# USB_UART.net
KiCad netlist of a schematic drawn in Altium Designer
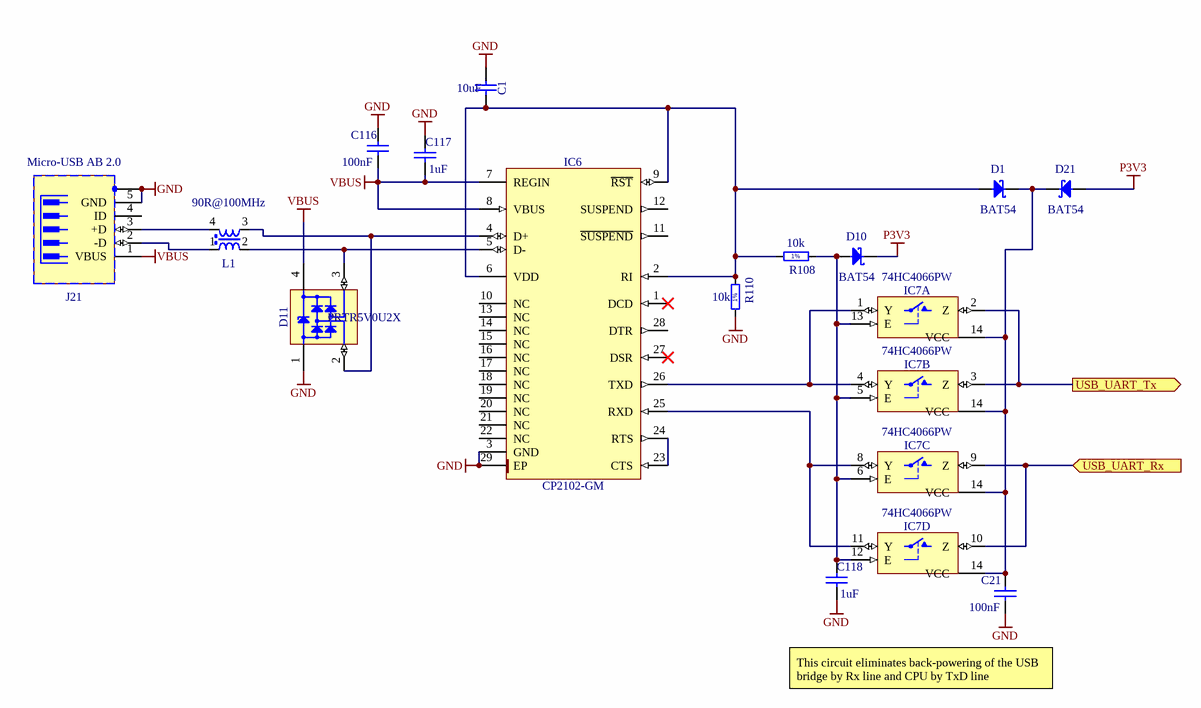
[diagram p0: USB_UART.SchDoc]

(export (version "E")
  (design (tool "Eeschema 10.0.6"))
  (components
    (comp (ref "C1")
      (value "10uF")
      (footprint "CAPC2012X135N")
      (description "Non-polarised capacitor")
      (fields
        (field (name "PART NUMBER") "CC0805_10UF_16V_10%_X5R")
        (field (name "VOLTAGE") "16V")
        (field (name "AUTHOR") "CERN DEM JLC")
      )
      (libsource (lib "Capacitors") (part "Capacitor - non polarized"))
    )
    (comp (ref "C21")
      (value "100nF")
      (footprint "CAPC1005X55N")
      (description "Non-polarised capacitor")
      (fields
        (field (name "PART NUMBER") "CC0402_100NF_16V_10%_X5R")
        (field (name "VOLTAGE") "16V")
        (field (name "AUTHOR") "CERN DEM JLC")
      )
      (libsource (lib "Capacitors") (part "Capacitor - non polarized"))
    )
    (comp (ref "C116")
      (value "100nF")
      (footprint "CAPC1005X55N")
      (description "Non-polarised capacitor")
      (fields
        (field (name "PART NUMBER") "CC0402_100NF_16V_10%_X5R")
        (field (name "VOLTAGE") "16V")
        (field (name "AUTHOR") "CERN DEM JLC")
      )
      (libsource (lib "Capacitors") (part "Capacitor - non polarized"))
    )
    (comp (ref "C117")
      (value "1uF")
      (footprint "CAPC1005X55N")
      (description "Non-polarised capacitor")
      (fields
        (field (name "PART NUMBER") "CC0402_1UF_16V_10%_X5R")
        (field (name "VOLTAGE") "16V")
        (field (name "AUTHOR") "CERN DEM JLC")
      )
      (libsource (lib "Capacitors") (part "Capacitor - non polarized"))
    )
    (comp (ref "C118")
      (value "1uF")
      (footprint "CAPC1005X55N")
      (description "Non-polarised capacitor")
      (fields
        (field (name "PART NUMBER") "CC0402_1UF_16V_10%_X5R")
        (field (name "VOLTAGE") "16V")
        (field (name "AUTHOR") "CERN DEM JLC")
      )
      (libsource (lib "Capacitors") (part "Capacitor - non polarized"))
    )
    (comp (ref "D1")
      (value "BAT54")
      (footprint "SOT95P240X130-3N")
      (description "Diode Schottky  Anode Pin 1 Cathode Pin 3 (Pas de pin 2)")
      (fields
        (field (name "VOLTAGE") "30V")
        (field (name "POWER") "200mA")
        (field (name "AUTHOR") "CERN DEM JLC")
      )
      (libsource (lib "ICs And Semiconductors") (part "Diode Schottky A1C3"))
    )
    (comp (ref "D10")
      (value "BAT54")
      (footprint "SOT95P240X130-3N")
      (description "Diode Schottky  Anode Pin 1 Cathode Pin 3 (Pas de pin 2)")
      (fields
        (field (name "VOLTAGE") "30V")
        (field (name "POWER") "200mA")
        (field (name "AUTHOR") "CERN DEM JLC")
      )
      (libsource (lib "ICs And Semiconductors") (part "Diode Schottky A1C3"))
    )
    (comp (ref "D11")
      (value "PRTR5V0U2X")
      (footprint "SOT190P230X110-4N")
      (description "Ultra Low Capacitance Double Rail-to-Rail ESD Protection Diode")
      (fields
        (field (name "VOLTAGE") "5.5V")
        (field (name "MANUFACTURER") "NXP SEMICONDUCTORS")
        (field (name "AUTHOR") "CERN DEM JLC")
      )
      (libsource (lib "ICs And Semiconductors") (part "PRTR5V0U2X"))
    )
    (comp (ref "D21")
      (value "BAT54")
      (footprint "SOT95P240X130-3N")
      (description "Diode Schottky  Anode Pin 1 Cathode Pin 3 (Pas de pin 2)")
      (fields
        (field (name "VOLTAGE") "30V")
        (field (name "POWER") "200mA")
        (field (name "AUTHOR") "CERN DEM JLC")
      )
      (libsource (lib "ICs And Semiconductors") (part "Diode Schottky A1C3"))
    )
    (comp (ref "IC6")
      (value "CP2102-GM")
      (footprint "QFN50P500X500X100-29N-S335")
      (description "Single-Chip USB to UART Bridge")
      (fields (field (name "MANUFACTURER") "SILICON LABS") (field (name "AUTHOR") "CERN DEM JLC"))
      (libsource (lib "ICs And Semiconductors") (part "CP2102-GM"))
    )
    (comp (ref "IC7")
      (value "74HC4066PW")
      (footprint "SOP65P640X110-14N")
      (fields (field (name "MANUFACTURER") "NXP SEMICONDUCTORS") (field (name "AUTHOR") "CERN DEM JLC"))
      (libsource (lib "ICs And Semiconductors") (part "4066"))
    )
    (comp (ref "J21")
      (value "Micro-USB AB 2.0")
      (footprint "HIROSE_ZX62RD-AB-5P8(30)")
      (description "5 Pin + 1 Shield USB Receptacle")
      (fields
        (field (name "PART NUMBER") "HIROSE_ZX62RD-AB-5P8(30)")
        (field (name "MANUFACTURER") "HIROSE (HRS)")
        (field (name "AUTHOR") "CERN DEM JMW")
      )
      (libsource (lib "Connectors") (part "Connector USB 5 Pin + 1Shield"))
    )
    (comp (ref "L1")
      (value "90R@100MHz")
      (footprint "IND_MURATA_DLW21S")
      (description "Inductor Common Mode")
      (fields
        (field (name "PART NUMBER") "IND_MURATA_DLW21SN900SQ2L")
        (field (name "POWER") "330mA")
        (field (name "AUTHOR") "CERN DEM JLC")
      )
      (libsource (lib "Inductors & Transformers") (part "Inductor Common Mode 1Dot-2 4Dot-3"))
    )
    (comp (ref "R108")
      (value "10k")
      (footprint "RESC1005X40N")
      (description "Resistor - 1%")
      (fields
        (field (name "PART NUMBER") "R0402_10K_1%_0.0625W_100PPM")
        (field (name "POWER") "0.0625W")
        (field (name "AUTHOR") "CERN DEM JLC")
      )
      (libsource (lib "Resistors") (part "Resistor - 1%"))
    )
    (comp (ref "R110")
      (value "10k")
      (footprint "RESC1005X40N")
      (description "Resistor - 1%")
      (fields
        (field (name "PART NUMBER") "R0402_10K_1%_0.0625W_100PPM")
        (field (name "POWER") "0.0625W")
        (field (name "AUTHOR") "CERN DEM JLC")
      )
      (libsource (lib "Resistors") (part "Resistor - 1%"))
    )
  )
  (nets
    (net (code "1") (name "/USB_UART_Rx") (class "Default")
      (node (ref "IC7") (pin "10") (pinfunction "Z_10") (pintype "bidirectional"))
      (node (ref "IC7") (pin "9") (pinfunction "Z_9") (pintype "bidirectional"))
    )
    (net (code "2") (name "/USB_UART_Tx") (class "Default")
      (node (ref "IC7") (pin "2") (pinfunction "Z_2") (pintype "bidirectional"))
      (node (ref "IC7") (pin "3") (pinfunction "Z_3") (pintype "bidirectional"))
    )
    (net (code "3") (name "GND") (class "Default")
      (node (ref "C1") (pin "1") (pinfunction "1_1") (pintype "passive"))
      (node (ref "C116") (pin "2") (pinfunction "2_2") (pintype "passive"))
      (node (ref "C117") (pin "1") (pinfunction "1_1") (pintype "passive"))
      (node (ref "C118") (pin "2") (pinfunction "2_2") (pintype "passive"))
      (node (ref "C21") (pin "1") (pinfunction "1_1") (pintype "passive"))
      (node (ref "D11") (pin "1") (pinfunction "GND_1") (pintype "power_in"))
      (node (ref "IC6") (pin "29") (pinfunction "EP_29") (pintype "power_in"))
      (node (ref "IC6") (pin "3") (pinfunction "GND_3") (pintype "power_in"))
      (node (ref "IC7") (pin "7") (pinfunction "GND_7") (pintype "power_in"))
      (node (ref "J21") (pin "5") (pinfunction "GND_5") (pintype "power_in"))
      (node (ref "J21") (pin "6") (pinfunction "SH_6") (pintype "power_in"))
      (node (ref "R110") (pin "1") (pinfunction "1_1") (pintype "passive"))
    )
    (net (code "4") (name "Net-(D1-A)") (class "Default")
      (node (ref "C1") (pin "2") (pinfunction "2_2") (pintype "passive"))
      (node (ref "D1") (pin "1") (pinfunction "A_1") (pintype "passive"))
      (node (ref "IC6") (pin "2") (pinfunction "RI_2") (pintype "input"))
      (node (ref "IC6") (pin "6") (pinfunction "VDD_6") (pintype "power_in"))
      (node (ref "IC6") (pin "9") (pinfunction "~{RST}_9") (pintype "bidirectional"))
      (node (ref "R108") (pin "1") (pinfunction "1_1") (pintype "passive"))
      (node (ref "R110") (pin "2") (pinfunction "2_2") (pintype "passive"))
    )
    (net (code "5") (name "Net-(D1-C)") (class "Default")
      (node (ref "C21") (pin "2") (pinfunction "2_2") (pintype "passive"))
      (node (ref "D1") (pin "3") (pinfunction "C_3") (pintype "passive"))
      (node (ref "D21") (pin "3") (pinfunction "C_3") (pintype "passive"))
      (node (ref "IC7") (pin "14") (pinfunction "VCC_14") (pintype "power_in"))
    )
    (net (code "6") (name "Net-(D10-A)") (class "Default")
      (node (ref "C118") (pin "1") (pinfunction "1_1") (pintype "passive"))
      (node (ref "D10") (pin "1") (pinfunction "A_1") (pintype "passive"))
      (node (ref "IC7") (pin "12") (pinfunction "E_12") (pintype "input"))
      (node (ref "IC7") (pin "13") (pinfunction "E_13") (pintype "input"))
      (node (ref "IC7") (pin "5") (pinfunction "E_5") (pintype "input"))
      (node (ref "IC7") (pin "6") (pinfunction "E_6") (pintype "input"))
      (node (ref "R108") (pin "2") (pinfunction "2_2") (pintype "passive"))
    )
    (net (code "7") (name "Net-(D11-I{slash}O1)") (class "Default")
      (node (ref "D11") (pin "2") (pinfunction "I/O1_2") (pintype "bidirectional"))
      (node (ref "IC6") (pin "4") (pinfunction "D+_4") (pintype "bidirectional"))
      (node (ref "L1") (pin "3") (pinfunction "3_3") (pintype "passive"))
    )
    (net (code "8") (name "Net-(D11-I{slash}O2)") (class "Default")
      (node (ref "D11") (pin "3") (pinfunction "I/O2_3") (pintype "bidirectional"))
      (node (ref "IC6") (pin "5") (pinfunction "D-_5") (pintype "bidirectional"))
      (node (ref "L1") (pin "2") (pinfunction "2_2") (pintype "passive"))
    )
    (net (code "9") (name "Net-(IC6-CTS)") (class "Default")
      (node (ref "IC6") (pin "23") (pinfunction "CTS_23") (pintype "input"))
      (node (ref "IC6") (pin "24") (pinfunction "RTS_24") (pintype "output"))
    )
    (net (code "10") (name "Net-(IC6-RXD)") (class "Default")
      (node (ref "IC6") (pin "25") (pinfunction "RXD_25") (pintype "input"))
      (node (ref "IC7") (pin "11") (pinfunction "Y_11") (pintype "bidirectional"))
      (node (ref "IC7") (pin "8") (pinfunction "Y_8") (pintype "bidirectional"))
    )
    (net (code "11") (name "Net-(IC6-TXD)") (class "Default")
      (node (ref "IC6") (pin "26") (pinfunction "TXD_26") (pintype "output"))
      (node (ref "IC7") (pin "1") (pinfunction "Y_1") (pintype "bidirectional"))
      (node (ref "IC7") (pin "4") (pinfunction "Y_4") (pintype "bidirectional"))
    )
    (net (code "12") (name "Net-(J21-+D)") (class "Default")
      (node (ref "J21") (pin "3") (pinfunction "+D_3") (pintype "bidirectional"))
      (node (ref "L1") (pin "4") (pinfunction "4_4") (pintype "passive"))
    )
    (net (code "13") (name "Net-(J21--D)") (class "Default")
      (node (ref "J21") (pin "2") (pinfunction "-D_2") (pintype "bidirectional"))
      (node (ref "L1") (pin "1") (pinfunction "1_1") (pintype "passive"))
    )
    (net (code "14") (name "P3V3") (class "Default")
      (node (ref "D10") (pin "3") (pinfunction "C_3") (pintype "passive"))
      (node (ref "D21") (pin "1") (pinfunction "A_1") (pintype "passive"))
    )
    (net (code "15") (name "VBUS") (class "Default")
      (node (ref "C116") (pin "1") (pinfunction "1_1") (pintype "passive"))
      (node (ref "C117") (pin "2") (pinfunction "2_2") (pintype "passive"))
      (node (ref "D11") (pin "4") (pinfunction "VCC_4") (pintype "power_in"))
      (node (ref "IC6") (pin "7") (pinfunction "REGIN_7") (pintype "power_in"))
      (node (ref "IC6") (pin "8") (pinfunction "VBUS_8") (pintype "input"))
      (node (ref "J21") (pin "1") (pinfunction "VBUS_1") (pintype "power_in"))
    )
    (net (code "16") (name "unconnected-(IC6-DCD-Pad1)") (class "Default")
      (node (ref "IC6") (pin "1") (pinfunction "DCD_1") (pintype "input+no_connect"))
    )
    (net (code "17") (name "unconnected-(IC6-DSR-Pad27)") (class "Default")
      (node (ref "IC6") (pin "27") (pinfunction "DSR_27") (pintype "input+no_connect"))
    )
    (net (code "18") (name "unconnected-(IC6-DTR-Pad28)") (class "Default")
      (node (ref "IC6") (pin "28") (pinfunction "DTR_28") (pintype "output"))
    )
    (net (code "19") (name "unconnected-(IC6-NC-Pad10)") (class "Default")
      (node (ref "IC6") (pin "10") (pinfunction "NC_10") (pintype "passive"))
    )
    (net (code "20") (name "unconnected-(IC6-NC-Pad13)") (class "Default")
      (node (ref "IC6") (pin "13") (pinfunction "NC_13") (pintype "passive"))
    )
    (net (code "21") (name "unconnected-(IC6-NC-Pad14)") (class "Default")
      (node (ref "IC6") (pin "14") (pinfunction "NC_14") (pintype "passive"))
    )
    (net (code "22") (name "unconnected-(IC6-NC-Pad15)") (class "Default")
      (node (ref "IC6") (pin "15") (pinfunction "NC_15") (pintype "passive"))
    )
    (net (code "23") (name "unconnected-(IC6-NC-Pad16)") (class "Default")
      (node (ref "IC6") (pin "16") (pinfunction "NC_16") (pintype "passive"))
    )
    (net (code "24") (name "unconnected-(IC6-NC-Pad17)") (class "Default")
      (node (ref "IC6") (pin "17") (pinfunction "NC_17") (pintype "passive"))
    )
    (net (code "25") (name "unconnected-(IC6-NC-Pad18)") (class "Default")
      (node (ref "IC6") (pin "18") (pinfunction "NC_18") (pintype "passive"))
    )
    (net (code "26") (name "unconnected-(IC6-NC-Pad19)") (class "Default")
      (node (ref "IC6") (pin "19") (pinfunction "NC_19") (pintype "passive"))
    )
    (net (code "27") (name "unconnected-(IC6-NC-Pad20)") (class "Default")
      (node (ref "IC6") (pin "20") (pinfunction "NC_20") (pintype "passive"))
    )
    (net (code "28") (name "unconnected-(IC6-NC-Pad21)") (class "Default")
      (node (ref "IC6") (pin "21") (pinfunction "NC_21") (pintype "passive"))
    )
    (net (code "29") (name "unconnected-(IC6-NC-Pad22)") (class "Default")
      (node (ref "IC6") (pin "22") (pinfunction "NC_22") (pintype "passive"))
    )
    (net (code "30") (name "unconnected-(IC6-SUSPEND-Pad12)") (class "Default")
      (node (ref "IC6") (pin "12") (pinfunction "SUSPEND_12") (pintype "output"))
    )
    (net (code "31") (name "unconnected-(IC6-~{SUSPEND}-Pad11)") (class "Default")
      (node (ref "IC6") (pin "11") (pinfunction "~{SUSPEND}_11") (pintype "output"))
    )
    (net (code "32") (name "unconnected-(J21-ID-Pad4)") (class "Default")
      (node (ref "J21") (pin "4") (pinfunction "ID_4") (pintype "passive"))
    )
  )
)
